# Nixie_power_supply_v1_0_1.net
KiCad netlist of a schematic drawn in EAGLE
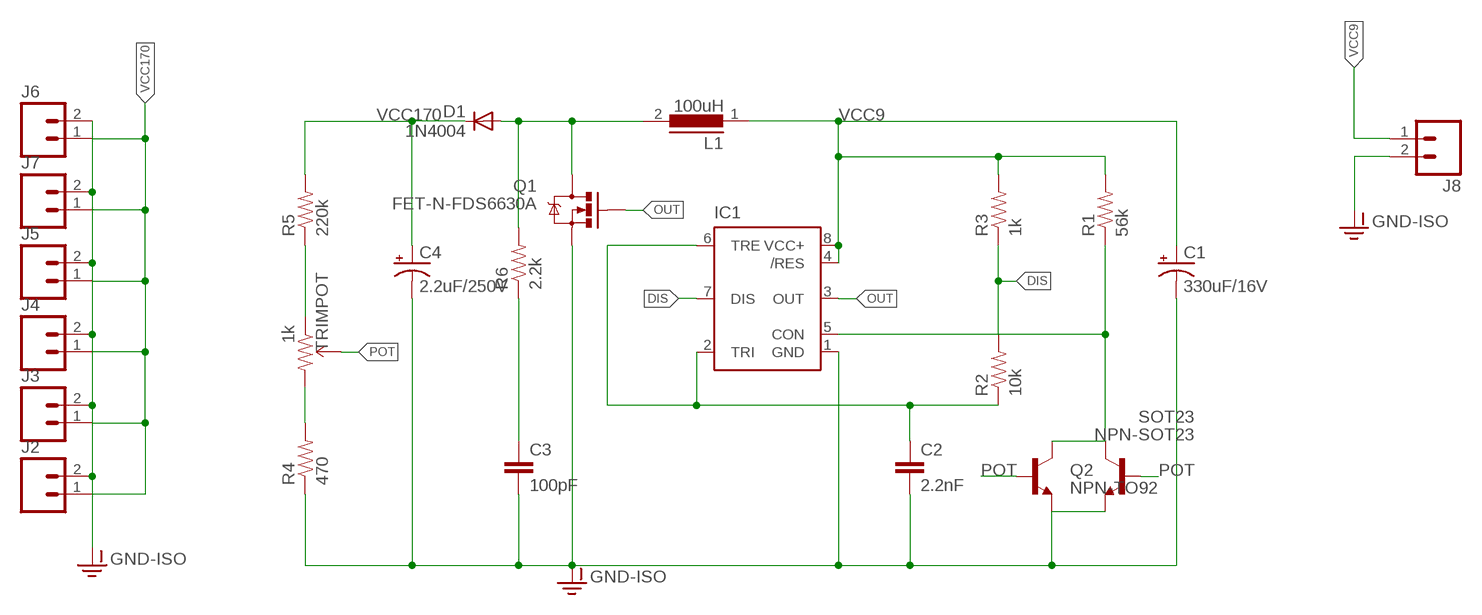
[diagram p0: schematic, sheet 1]

(export (version "E")
  (design (tool "Eeschema 10.0.6"))
  (components
    (comp (ref "C1")
      (value "330uF/16V")
      (footprint "eagle-import:E3,5-8")
      (libsource (lib "eagle-import") (part "CPOL-USE3.5-8"))
    )
    (comp (ref "C2")
      (value "2.2nF")
      (footprint "eagle-import:0805")
      (libsource (lib "eagle-import") (part "CAP0805"))
    )
    (comp (ref "C3")
      (value "100pF")
      (footprint "eagle-import:C1005")
      (libsource (lib "eagle-import") (part "C-EUC1005"))
    )
    (comp (ref "C4")
      (value "2.2uF/250V")
      (footprint "eagle-import:CPOL-RADIAL-100UF-25V")
      (libsource (lib "eagle-import") (part "CAP_POLPTH1"))
    )
    (comp (ref "D1")
      (value "1N4004")
      (footprint "eagle-import:DO41-10")
      (libsource (lib "eagle-import") (part "1N4004"))
    )
    (comp (ref "IC1")
      (value "NE555D")
      (footprint "eagle-import:SO08")
      (libsource (lib "eagle-import") (part "NE555D"))
    )
    (comp (ref "J2")
      (value "M02LOCK")
      (footprint "eagle-import:1X02_LOCK")
      (libsource (lib "eagle-import") (part "M02LOCK"))
    )
    (comp (ref "J3")
      (value "M02LOCK")
      (footprint "eagle-import:1X02_LOCK")
      (libsource (lib "eagle-import") (part "M02LOCK"))
    )
    (comp (ref "J4")
      (value "M02LOCK")
      (footprint "eagle-import:1X02_LOCK")
      (libsource (lib "eagle-import") (part "M02LOCK"))
    )
    (comp (ref "J5")
      (value "M02LOCK")
      (footprint "eagle-import:1X02_LOCK")
      (libsource (lib "eagle-import") (part "M02LOCK"))
    )
    (comp (ref "J6")
      (value "M02LOCK")
      (footprint "eagle-import:1X02_LOCK")
      (libsource (lib "eagle-import") (part "M02LOCK"))
    )
    (comp (ref "J7")
      (value "M02LOCK")
      (footprint "eagle-import:1X02_LOCK")
      (libsource (lib "eagle-import") (part "M02LOCK"))
    )
    (comp (ref "J8")
      (value "M02LOCK")
      (footprint "eagle-import:1X02_LOCK")
      (libsource (lib "eagle-import") (part "M02LOCK"))
    )
    (comp (ref "L1")
      (value "100uH")
      (footprint "eagle-import:DR74")
      (libsource (lib "eagle-import") (part "DR74"))
    )
    (comp (ref "Q1")
      (value "FET-N-FDS6630A")
      (footprint "eagle-import:SO08")
      (libsource (lib "eagle-import") (part "MOSFET-NCHANNELFDS6630A"))
    )
    (comp (ref "Q2")
      (value "NPN-TO92")
      (footprint "eagle-import:TO-92-AMMO")
      (libsource (lib "eagle-import") (part "TRANSISTOR_NPNBC547"))
    )
    (comp (ref "R1")
      (value "56k")
      (footprint "eagle-import:0805")
      (libsource (lib "eagle-import") (part "RESISTOR0805-RES"))
    )
    (comp (ref "R2")
      (value "10k")
      (footprint "eagle-import:0805")
      (libsource (lib "eagle-import") (part "RESISTOR0805-RES"))
    )
    (comp (ref "R3")
      (value "1k")
      (footprint "eagle-import:0805")
      (libsource (lib "eagle-import") (part "RESISTOR0805-RES"))
    )
    (comp (ref "R4")
      (value "470")
      (footprint "eagle-import:0805")
      (libsource (lib "eagle-import") (part "RESISTOR0805-RES"))
    )
    (comp (ref "R5")
      (value "220k")
      (footprint "eagle-import:0805")
      (libsource (lib "eagle-import") (part "RESISTOR0805-RES"))
    )
    (comp (ref "R6")
      (value "2.2k")
      (footprint "eagle-import:0805")
      (libsource (lib "eagle-import") (part "RESISTOR0805-RES"))
    )
    (comp (ref "SOT23")
      (value "NPN-SOT23")
      (footprint "eagle-import:SOT23-BEC")
      (libsource (lib "eagle-import") (part "-NPN-SOT23-BECBC817-16"))
    )
    (comp (ref "TRIMPOT")
      (value "1k")
      (footprint "eagle-import:TRIMPOT_TC33")
      (libsource (lib "eagle-import") (part "TRIMPOT-2"))
    )
  )
  (nets
    (net (code "1") (name "DIS") (class "Default")
      (node (ref "IC1") (pin "7") (pinfunction "DIS_7") (pintype "input"))
      (node (ref "R2") (pin "2") (pinfunction "2_2") (pintype "passive"))
      (node (ref "R3") (pin "1") (pinfunction "1_1") (pintype "passive"))
    )
    (net (code "2") (name "GND-ISO") (class "Default")
      (node (ref "C1") (pin "-") (pinfunction "-_-") (pintype "passive"))
      (node (ref "C2") (pin "2") (pinfunction "2_2") (pintype "passive"))
      (node (ref "C3") (pin "2") (pinfunction "2_2") (pintype "passive"))
      (node (ref "C4") (pin "2") (pinfunction "-_2") (pintype "passive"))
      (node (ref "IC1") (pin "1") (pinfunction "GND_1") (pintype "power_in"))
      (node (ref "J2") (pin "2") (pinfunction "2_2") (pintype "passive"))
      (node (ref "J3") (pin "2") (pinfunction "2_2") (pintype "passive"))
      (node (ref "J4") (pin "2") (pinfunction "2_2") (pintype "passive"))
      (node (ref "J5") (pin "2") (pinfunction "2_2") (pintype "passive"))
      (node (ref "J6") (pin "2") (pinfunction "2_2") (pintype "passive"))
      (node (ref "J7") (pin "2") (pinfunction "2_2") (pintype "passive"))
      (node (ref "J8") (pin "2") (pinfunction "2_2") (pintype "passive"))
      (node (ref "Q1") (pin "1") (pinfunction "S_1") (pintype "passive"))
      (node (ref "Q1") (pin "2") (pinfunction "S_2") (pintype "passive"))
      (node (ref "Q1") (pin "3") (pinfunction "S_3") (pintype "passive"))
      (node (ref "Q2") (pin "3") (pinfunction "E_3") (pintype "passive"))
      (node (ref "R4") (pin "1") (pinfunction "1_1") (pintype "passive"))
      (node (ref "SOT23") (pin "E") (pinfunction "E_E") (pintype "passive"))
    )
    (net (code "3") (name "Net-(C3-Pad1)") (class "Default")
      (node (ref "C3") (pin "1") (pinfunction "1_1") (pintype "passive"))
      (node (ref "R6") (pin "1") (pinfunction "1_1") (pintype "passive"))
    )
    (net (code "4") (name "Net-(D1-PadA)") (class "Default")
      (node (ref "D1") (pin "A") (pinfunction "A_A") (pintype "passive"))
      (node (ref "L1") (pin "2") (pinfunction "2_2") (pintype "passive"))
      (node (ref "Q1") (pin "5") (pinfunction "D_5") (pintype "passive"))
      (node (ref "Q1") (pin "6") (pinfunction "D_6") (pintype "passive"))
      (node (ref "Q1") (pin "7") (pinfunction "D_7") (pintype "passive"))
      (node (ref "Q1") (pin "8") (pinfunction "D_8") (pintype "passive"))
      (node (ref "R6") (pin "2") (pinfunction "2_2") (pintype "passive"))
    )
    (net (code "5") (name "Net-(IC1-CON)") (class "Default")
      (node (ref "IC1") (pin "5") (pinfunction "CON_5") (pintype "input"))
      (node (ref "Q2") (pin "1") (pinfunction "C_1") (pintype "passive"))
      (node (ref "R1") (pin "1") (pinfunction "1_1") (pintype "passive"))
      (node (ref "SOT23") (pin "C") (pinfunction "C_C") (pintype "passive"))
    )
    (net (code "6") (name "Net-(IC1-TRE)") (class "Default")
      (node (ref "C2") (pin "1") (pinfunction "1_1") (pintype "passive"))
      (node (ref "IC1") (pin "2") (pinfunction "TRI_2") (pintype "input"))
      (node (ref "IC1") (pin "6") (pinfunction "TRE_6") (pintype "input"))
      (node (ref "R2") (pin "1") (pinfunction "1_1") (pintype "passive"))
    )
    (net (code "7") (name "Net-(TRIMPOT-CCW)") (class "Default")
      (node (ref "R5") (pin "1") (pinfunction "1_1") (pintype "passive"))
      (node (ref "TRIMPOT") (pin "1") (pinfunction "CCW_1") (pintype "passive"))
    )
    (net (code "8") (name "Net-(TRIMPOT-CW)") (class "Default")
      (node (ref "R4") (pin "2") (pinfunction "2_2") (pintype "passive"))
      (node (ref "TRIMPOT") (pin "3") (pinfunction "CW_3") (pintype "passive"))
    )
    (net (code "9") (name "OUT") (class "Default")
      (node (ref "IC1") (pin "3") (pinfunction "OUT_3") (pintype "output"))
      (node (ref "Q1") (pin "4") (pinfunction "G_4") (pintype "passive"))
    )
    (net (code "10") (name "POT") (class "Default")
      (node (ref "Q2") (pin "2") (pinfunction "B_2") (pintype "passive"))
      (node (ref "SOT23") (pin "B") (pinfunction "B_B") (pintype "passive"))
      (node (ref "TRIMPOT") (pin "2") (pinfunction "WIPER_2") (pintype "passive"))
    )
    (net (code "11") (name "VCC9") (class "Default")
      (node (ref "C1") (pin "+") (pinfunction "+_+") (pintype "passive"))
      (node (ref "IC1") (pin "4") (pinfunction "/RES_4") (pintype "input"))
      (node (ref "IC1") (pin "8") (pinfunction "VCC+_8") (pintype "power_in"))
      (node (ref "J8") (pin "1") (pinfunction "1_1") (pintype "passive"))
      (node (ref "L1") (pin "1") (pinfunction "1_1") (pintype "passive"))
      (node (ref "R1") (pin "2") (pinfunction "2_2") (pintype "passive"))
      (node (ref "R3") (pin "2") (pinfunction "2_2") (pintype "passive"))
    )
    (net (code "12") (name "VCC170") (class "Default")
      (node (ref "C4") (pin "1") (pinfunction "+_1") (pintype "passive"))
      (node (ref "D1") (pin "C") (pinfunction "C_C") (pintype "passive"))
      (node (ref "J2") (pin "1") (pinfunction "1_1") (pintype "passive"))
      (node (ref "J3") (pin "1") (pinfunction "1_1") (pintype "passive"))
      (node (ref "J4") (pin "1") (pinfunction "1_1") (pintype "passive"))
      (node (ref "J5") (pin "1") (pinfunction "1_1") (pintype "passive"))
      (node (ref "J6") (pin "1") (pinfunction "1_1") (pintype "passive"))
      (node (ref "J7") (pin "1") (pinfunction "1_1") (pintype "passive"))
      (node (ref "R5") (pin "2") (pinfunction "2_2") (pintype "passive"))
    )
  )
)
